# MCU063B_Emulator_interface.net
KiCad netlist of a schematic drawn in Altium Designer
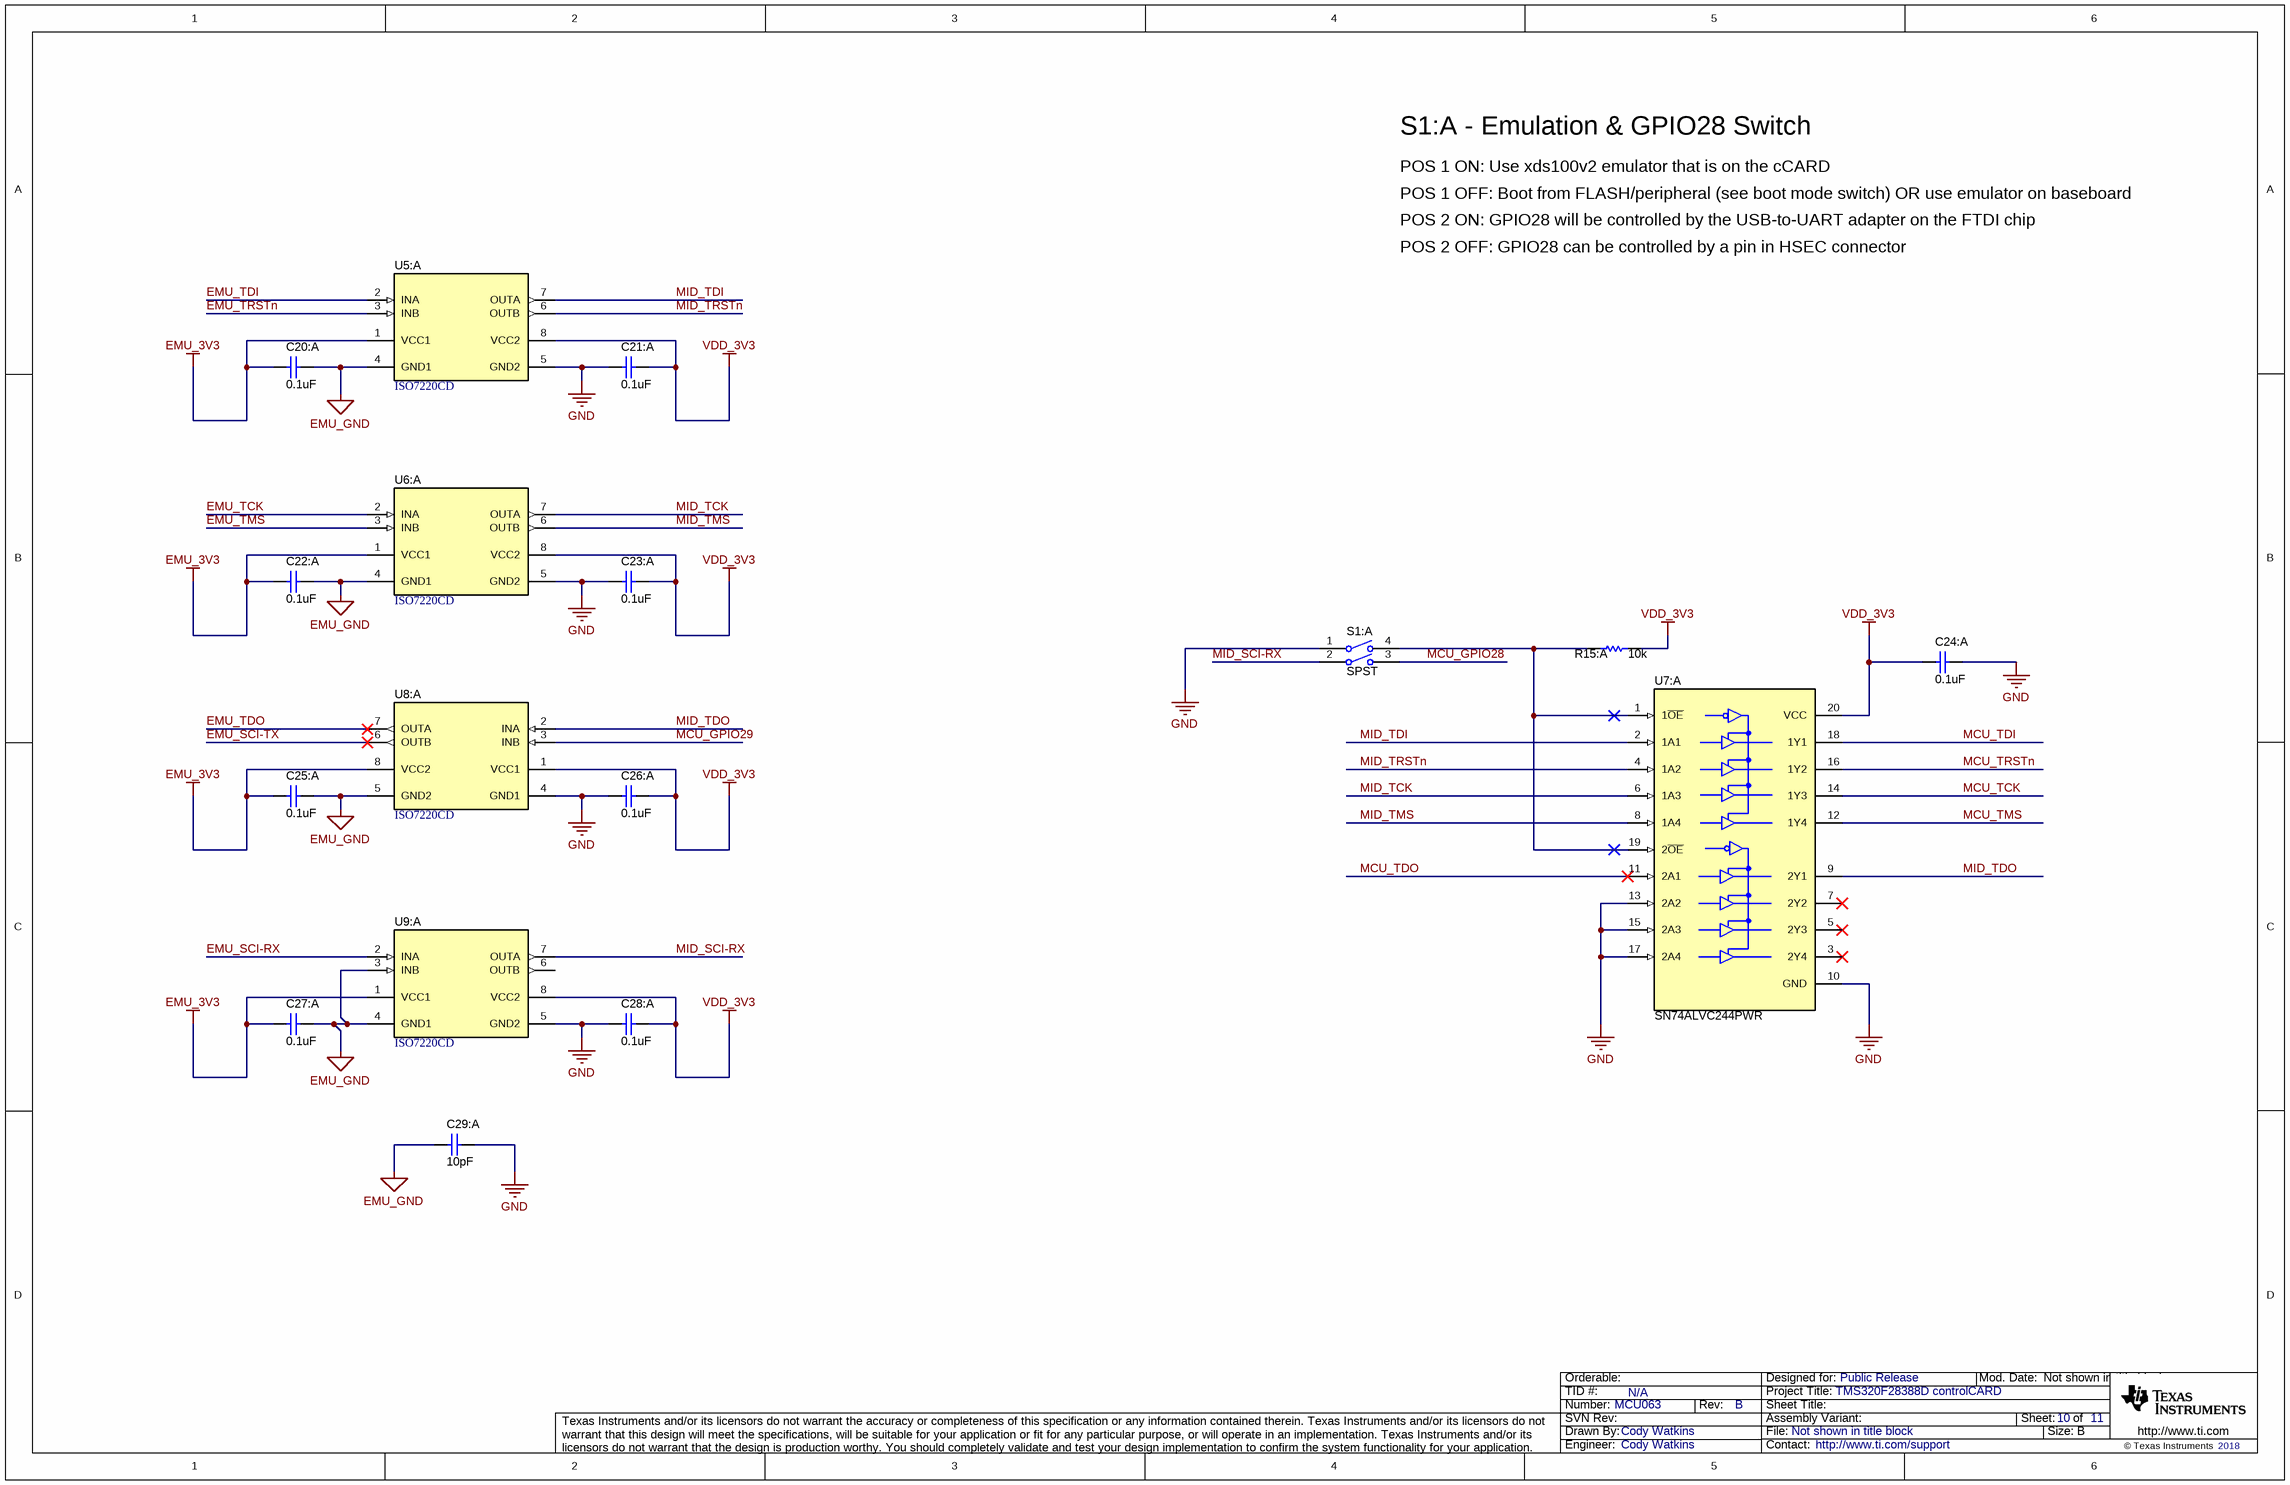
[diagram p0: MCU063B_Emulator_interface.SchDoc]

(export (version "E")
  (design (tool "Eeschema 10.0.6"))
  (components
    (comp (ref "C20:A")
      (value "CL05B104KP5NNNC")
      (footprint "0402")
      (description "CAP, CERM, 0.1 uF, 10 V, +/- 10%, X7R, 0402")
      (fields
        (field (name "VALUEDISPLAYED") "0.1uF")
        (field (name "MANUFACTURER") "Samsung Electro-Mechanics")
        (field (name "PUBLISHER") "Texas Instruments")
      )
      (libsource (lib "Altium Vault - TI") (part "Capacitor"))
    )
    (comp (ref "C21:A")
      (value "CL05B104KP5NNNC")
      (footprint "0402")
      (description "CAP, CERM, 0.1 uF, 10 V, +/- 10%, X7R, 0402")
      (fields
        (field (name "VALUEDISPLAYED") "0.1uF")
        (field (name "MANUFACTURER") "Samsung Electro-Mechanics")
        (field (name "PUBLISHER") "Texas Instruments")
      )
      (libsource (lib "Altium Vault - TI") (part "Capacitor"))
    )
    (comp (ref "C22:A")
      (value "CL05B104KP5NNNC")
      (footprint "0402")
      (description "CAP, CERM, 0.1 uF, 10 V, +/- 10%, X7R, 0402")
      (fields
        (field (name "VALUEDISPLAYED") "0.1uF")
        (field (name "MANUFACTURER") "Samsung Electro-Mechanics")
        (field (name "PUBLISHER") "Texas Instruments")
      )
      (libsource (lib "Altium Vault - TI") (part "Capacitor"))
    )
    (comp (ref "C23:A")
      (value "CL05B104KP5NNNC")
      (footprint "0402")
      (description "CAP, CERM, 0.1 uF, 10 V, +/- 10%, X7R, 0402")
      (fields
        (field (name "VALUEDISPLAYED") "0.1uF")
        (field (name "MANUFACTURER") "Samsung Electro-Mechanics")
        (field (name "PUBLISHER") "Texas Instruments")
      )
      (libsource (lib "Altium Vault - TI") (part "Capacitor"))
    )
    (comp (ref "C24:A")
      (value "CL05B104KP5NNNC")
      (footprint "0402")
      (description "CAP, CERM, 0.1 uF, 10 V, +/- 10%, X7R, 0402")
      (fields
        (field (name "VALUEDISPLAYED") "0.1uF")
        (field (name "MANUFACTURER") "Samsung Electro-Mechanics")
        (field (name "PUBLISHER") "Texas Instruments")
      )
      (libsource (lib "Altium Vault - TI") (part "Capacitor"))
    )
    (comp (ref "C25:A")
      (value "CL05B104KP5NNNC")
      (footprint "0402")
      (description "CAP, CERM, 0.1 uF, 10 V, +/- 10%, X7R, 0402")
      (fields
        (field (name "VALUEDISPLAYED") "0.1uF")
        (field (name "MANUFACTURER") "Samsung Electro-Mechanics")
        (field (name "PUBLISHER") "Texas Instruments")
      )
      (libsource (lib "Altium Vault - TI") (part "Capacitor"))
    )
    (comp (ref "C26:A")
      (value "CL05B104KP5NNNC")
      (footprint "0402")
      (description "CAP, CERM, 0.1 uF, 10 V, +/- 10%, X7R, 0402")
      (fields
        (field (name "VALUEDISPLAYED") "0.1uF")
        (field (name "MANUFACTURER") "Samsung Electro-Mechanics")
        (field (name "PUBLISHER") "Texas Instruments")
      )
      (libsource (lib "Altium Vault - TI") (part "Capacitor"))
    )
    (comp (ref "C27:A")
      (value "CL05B104KP5NNNC")
      (footprint "0402")
      (description "CAP, CERM, 0.1 uF, 10 V, +/- 10%, X7R, 0402")
      (fields
        (field (name "VALUEDISPLAYED") "0.1uF")
        (field (name "MANUFACTURER") "Samsung Electro-Mechanics")
        (field (name "PUBLISHER") "Texas Instruments")
      )
      (libsource (lib "Altium Vault - TI") (part "Capacitor"))
    )
    (comp (ref "C28:A")
      (value "CL05B104KP5NNNC")
      (footprint "0402")
      (description "CAP, CERM, 0.1 uF, 10 V, +/- 10%, X7R, 0402")
      (fields
        (field (name "VALUEDISPLAYED") "0.1uF")
        (field (name "MANUFACTURER") "Samsung Electro-Mechanics")
        (field (name "PUBLISHER") "Texas Instruments")
      )
      (libsource (lib "Altium Vault - TI") (part "Capacitor"))
    )
    (comp (ref "C29:A")
      (value "C1812C100JHGACTU")
      (footprint "1812_180")
      (description "CAP, CERM, 10 pF, 3000 V,+/- 5%, C0G/NP0, AEC-Q200 Grade 1, 1812")
      (fields (field (name "MANUFACTURER") "Kemet") (field (name "VALUEDISPLAYED") "10pF"))
      (libsource (lib "Altium Vault - TI") (part "Capacitor"))
    )
    (comp (ref "R15:A")
      (value "CRCW040210K0JNED")
      (footprint "0402")
      (description "RES, 10 k, 5%, 0.063 W, AEC-Q200 Grade 0, 0402")
      (fields (field (name "VALUEDISPLAYED") "10k") (field (name "MANUFACTURER") "Vishay-Dale"))
      (libsource (lib "Altium Vault - TI") (part "Resistor"))
    )
    (comp (ref "S1:A")
      (value "218-2LPST")
      (footprint "SW_218-2LP")
      (description "Switch, SPST, 2 Pos, 25mA, 24VDC, SMD")
      (fields
        (field (name "MANUFACTURER") "CTS Electrocomponents")
        (field (name "CIRCUIT") "SPST")
        (field (name "PUBLISHER") "Texas Instruments")
      )
      (libsource (lib "Altium Vault - TI") (part "SW_2SPST"))
    )
    (comp (ref "U5:A")
      (value "ISO7220CD")
      (footprint "D0008B_N")
      (fields (field (name "MANUFACTURER") "Texas Instruments"))
      (libsource (lib "Altium Vault - TI") (part "TI-ISO7220C-SOIC_D-8"))
    )
    (comp (ref "U6:A")
      (value "ISO7220CD")
      (footprint "D0008B_N")
      (fields (field (name "MANUFACTURER") "Texas Instruments"))
      (libsource (lib "Altium Vault - TI") (part "TI-ISO7220C-SOIC_D-8"))
    )
    (comp (ref "U7:A")
      (value "SN74ALVC244PWR")
      (footprint "PW0020A_N")
      (description "Octal Buffer/Driver With 3-State OUtputs, PW0020A (TSSOP-20)")
      (fields
        (field (name "MANUFACTURER") "Texas Instruments")
        (field (name "GENERIC PART NUMBER") "SN74ALVC244")
      )
      (libsource (lib "Altium Vault - TI") (part "SN74ALVC244PW"))
    )
    (comp (ref "U8:A")
      (value "ISO7220CD")
      (footprint "D0008B_N")
      (fields (field (name "MANUFACTURER") "Texas Instruments"))
      (libsource (lib "") (part "TI-ISO7220C-SOIC_D-8_1"))
    )
    (comp (ref "U9:A")
      (value "ISO7220CD")
      (footprint "D0008B_N")
      (fields (field (name "MANUFACTURER") "Texas Instruments"))
      (libsource (lib "Altium Vault - TI") (part "TI-ISO7220C-SOIC_D-8"))
    )
  )
  (nets
    (net (code "1") (name "/EMU_SCI-RX") (class "Default")
      (node (ref "U9:A") (pin "2") (pinfunction "INA_2") (pintype "input"))
    )
    (net (code "2") (name "/EMU_SCI-TX") (class "Default")
      (node (ref "U8:A") (pin "6") (pinfunction "OUTB_6") (pintype "output+no_connect"))
    )
    (net (code "3") (name "/EMU_TCK") (class "Default")
      (node (ref "U6:A") (pin "2") (pinfunction "INA_2") (pintype "input"))
    )
    (net (code "4") (name "/EMU_TDI") (class "Default")
      (node (ref "U5:A") (pin "2") (pinfunction "INA_2") (pintype "input"))
    )
    (net (code "5") (name "/EMU_TDO") (class "Default")
      (node (ref "U8:A") (pin "7") (pinfunction "OUTA_7") (pintype "output+no_connect"))
    )
    (net (code "6") (name "/EMU_TMS") (class "Default")
      (node (ref "U6:A") (pin "3") (pinfunction "INB_3") (pintype "input"))
    )
    (net (code "7") (name "/EMU_TRSTn") (class "Default")
      (node (ref "U5:A") (pin "3") (pinfunction "INB_3") (pintype "input"))
    )
    (net (code "8") (name "/MCU_GPIO28") (class "Default")
      (node (ref "S1:A") (pin "3") (pinfunction "3_3") (pintype "passive"))
    )
    (net (code "9") (name "/MCU_GPIO29") (class "Default")
      (node (ref "U8:A") (pin "3") (pinfunction "INB_3") (pintype "input"))
    )
    (net (code "10") (name "/MCU_TCK") (class "Default")
      (node (ref "U7:A") (pin "14") (pinfunction "1Y3_14") (pintype "tri_state"))
    )
    (net (code "11") (name "/MCU_TDI") (class "Default")
      (node (ref "U7:A") (pin "18") (pinfunction "1Y1_18") (pintype "tri_state"))
    )
    (net (code "12") (name "/MCU_TDO") (class "Default")
      (node (ref "U7:A") (pin "11") (pinfunction "2A1_11") (pintype "input+no_connect"))
    )
    (net (code "13") (name "/MCU_TMS") (class "Default")
      (node (ref "U7:A") (pin "12") (pinfunction "1Y4_12") (pintype "tri_state"))
    )
    (net (code "14") (name "/MCU_TRSTn") (class "Default")
      (node (ref "U7:A") (pin "16") (pinfunction "1Y2_16") (pintype "tri_state"))
    )
    (net (code "15") (name "/MID_SCI-RX") (class "Default")
      (node (ref "S1:A") (pin "2") (pinfunction "2_2") (pintype "passive"))
      (node (ref "U9:A") (pin "7") (pinfunction "OUTA_7") (pintype "output"))
    )
    (net (code "16") (name "/MID_TCK") (class "Default")
      (node (ref "U6:A") (pin "7") (pinfunction "OUTA_7") (pintype "output"))
      (node (ref "U7:A") (pin "6") (pinfunction "1A3_6") (pintype "input"))
    )
    (net (code "17") (name "/MID_TDI") (class "Default")
      (node (ref "U5:A") (pin "7") (pinfunction "OUTA_7") (pintype "output"))
      (node (ref "U7:A") (pin "2") (pinfunction "1A1_2") (pintype "input"))
    )
    (net (code "18") (name "/MID_TDO") (class "Default")
      (node (ref "U7:A") (pin "9") (pinfunction "2Y1_9") (pintype "tri_state"))
      (node (ref "U8:A") (pin "2") (pinfunction "INA_2") (pintype "input"))
    )
    (net (code "19") (name "/MID_TMS") (class "Default")
      (node (ref "U6:A") (pin "6") (pinfunction "OUTB_6") (pintype "output"))
      (node (ref "U7:A") (pin "8") (pinfunction "1A4_8") (pintype "input"))
    )
    (net (code "20") (name "/MID_TRSTn") (class "Default")
      (node (ref "U5:A") (pin "6") (pinfunction "OUTB_6") (pintype "output"))
      (node (ref "U7:A") (pin "4") (pinfunction "1A2_4") (pintype "input"))
    )
    (net (code "21") (name "EMU_3V3") (class "Default")
      (node (ref "C20:A") (pin "2") (pinfunction "2_2") (pintype "passive"))
      (node (ref "C22:A") (pin "2") (pinfunction "2_2") (pintype "passive"))
      (node (ref "C25:A") (pin "2") (pinfunction "2_2") (pintype "passive"))
      (node (ref "C27:A") (pin "2") (pinfunction "2_2") (pintype "passive"))
      (node (ref "U5:A") (pin "1") (pinfunction "VCC1_1") (pintype "power_in"))
      (node (ref "U6:A") (pin "1") (pinfunction "VCC1_1") (pintype "power_in"))
      (node (ref "U8:A") (pin "8") (pinfunction "VCC2_8") (pintype "power_in"))
      (node (ref "U9:A") (pin "1") (pinfunction "VCC1_1") (pintype "power_in"))
    )
    (net (code "22") (name "EMU_GND") (class "Default")
      (node (ref "C20:A") (pin "1") (pinfunction "1_1") (pintype "passive"))
      (node (ref "C22:A") (pin "1") (pinfunction "1_1") (pintype "passive"))
      (node (ref "C25:A") (pin "1") (pinfunction "1_1") (pintype "passive"))
      (node (ref "C27:A") (pin "1") (pinfunction "1_1") (pintype "passive"))
      (node (ref "C29:A") (pin "2") (pinfunction "2_2") (pintype "passive"))
      (node (ref "U5:A") (pin "4") (pinfunction "GND1_4") (pintype "power_in"))
      (node (ref "U6:A") (pin "4") (pinfunction "GND1_4") (pintype "power_in"))
      (node (ref "U8:A") (pin "5") (pinfunction "GND2_5") (pintype "power_in"))
      (node (ref "U9:A") (pin "3") (pinfunction "INB_3") (pintype "input"))
      (node (ref "U9:A") (pin "4") (pinfunction "GND1_4") (pintype "power_in"))
    )
    (net (code "23") (name "GND") (class "Default")
      (node (ref "C21:A") (pin "2") (pinfunction "2_2") (pintype "passive"))
      (node (ref "C23:A") (pin "2") (pinfunction "2_2") (pintype "passive"))
      (node (ref "C24:A") (pin "1") (pinfunction "1_1") (pintype "passive"))
      (node (ref "C26:A") (pin "2") (pinfunction "2_2") (pintype "passive"))
      (node (ref "C28:A") (pin "2") (pinfunction "2_2") (pintype "passive"))
      (node (ref "C29:A") (pin "1") (pinfunction "1_1") (pintype "passive"))
      (node (ref "S1:A") (pin "1") (pinfunction "1_1") (pintype "passive"))
      (node (ref "U5:A") (pin "5") (pinfunction "GND2_5") (pintype "power_in"))
      (node (ref "U6:A") (pin "5") (pinfunction "GND2_5") (pintype "power_in"))
      (node (ref "U7:A") (pin "10") (pinfunction "GND_10") (pintype "power_in"))
      (node (ref "U7:A") (pin "13") (pinfunction "2A2_13") (pintype "input"))
      (node (ref "U7:A") (pin "15") (pinfunction "2A3_15") (pintype "input"))
      (node (ref "U7:A") (pin "17") (pinfunction "2A4_17") (pintype "input"))
      (node (ref "U8:A") (pin "4") (pinfunction "GND1_4") (pintype "power_in"))
      (node (ref "U9:A") (pin "5") (pinfunction "GND2_5") (pintype "power_in"))
    )
    (net (code "24") (name "Net-(U7:A-1~{OE})") (class "Default")
      (node (ref "R15:A") (pin "1") (pinfunction "1_1") (pintype "passive"))
      (node (ref "S1:A") (pin "4") (pinfunction "4_4") (pintype "passive"))
      (node (ref "U7:A") (pin "1") (pinfunction "1~{OE}_1") (pintype "input"))
      (node (ref "U7:A") (pin "19") (pinfunction "2~{OE}_19") (pintype "input"))
    )
    (net (code "25") (name "VDD_3V3") (class "Default")
      (node (ref "C21:A") (pin "1") (pinfunction "1_1") (pintype "passive"))
      (node (ref "C23:A") (pin "1") (pinfunction "1_1") (pintype "passive"))
      (node (ref "C24:A") (pin "2") (pinfunction "2_2") (pintype "passive"))
      (node (ref "C26:A") (pin "1") (pinfunction "1_1") (pintype "passive"))
      (node (ref "C28:A") (pin "1") (pinfunction "1_1") (pintype "passive"))
      (node (ref "R15:A") (pin "2") (pinfunction "2_2") (pintype "passive"))
      (node (ref "U5:A") (pin "8") (pinfunction "VCC2_8") (pintype "power_in"))
      (node (ref "U6:A") (pin "8") (pinfunction "VCC2_8") (pintype "power_in"))
      (node (ref "U7:A") (pin "20") (pinfunction "VCC_20") (pintype "power_in"))
      (node (ref "U8:A") (pin "1") (pinfunction "VCC1_1") (pintype "power_in"))
      (node (ref "U9:A") (pin "8") (pinfunction "VCC2_8") (pintype "power_in"))
    )
    (net (code "26") (name "unconnected-(U7:A-2Y2-Pad7)") (class "Default")
      (node (ref "U7:A") (pin "7") (pinfunction "2Y2_7") (pintype "tri_state+no_connect"))
    )
    (net (code "27") (name "unconnected-(U7:A-2Y3-Pad5)") (class "Default")
      (node (ref "U7:A") (pin "5") (pinfunction "2Y3_5") (pintype "tri_state+no_connect"))
    )
    (net (code "28") (name "unconnected-(U7:A-2Y4-Pad3)") (class "Default")
      (node (ref "U7:A") (pin "3") (pinfunction "2Y4_3") (pintype "tri_state+no_connect"))
    )
    (net (code "29") (name "unconnected-(U9:A-OUTB-Pad6)") (class "Default")
      (node (ref "U9:A") (pin "6") (pinfunction "OUTB_6") (pintype "output"))
    )
  )
)
